# Qwiic_RockBLOCK_9603N.net
KiCad netlist of a schematic drawn in EAGLE
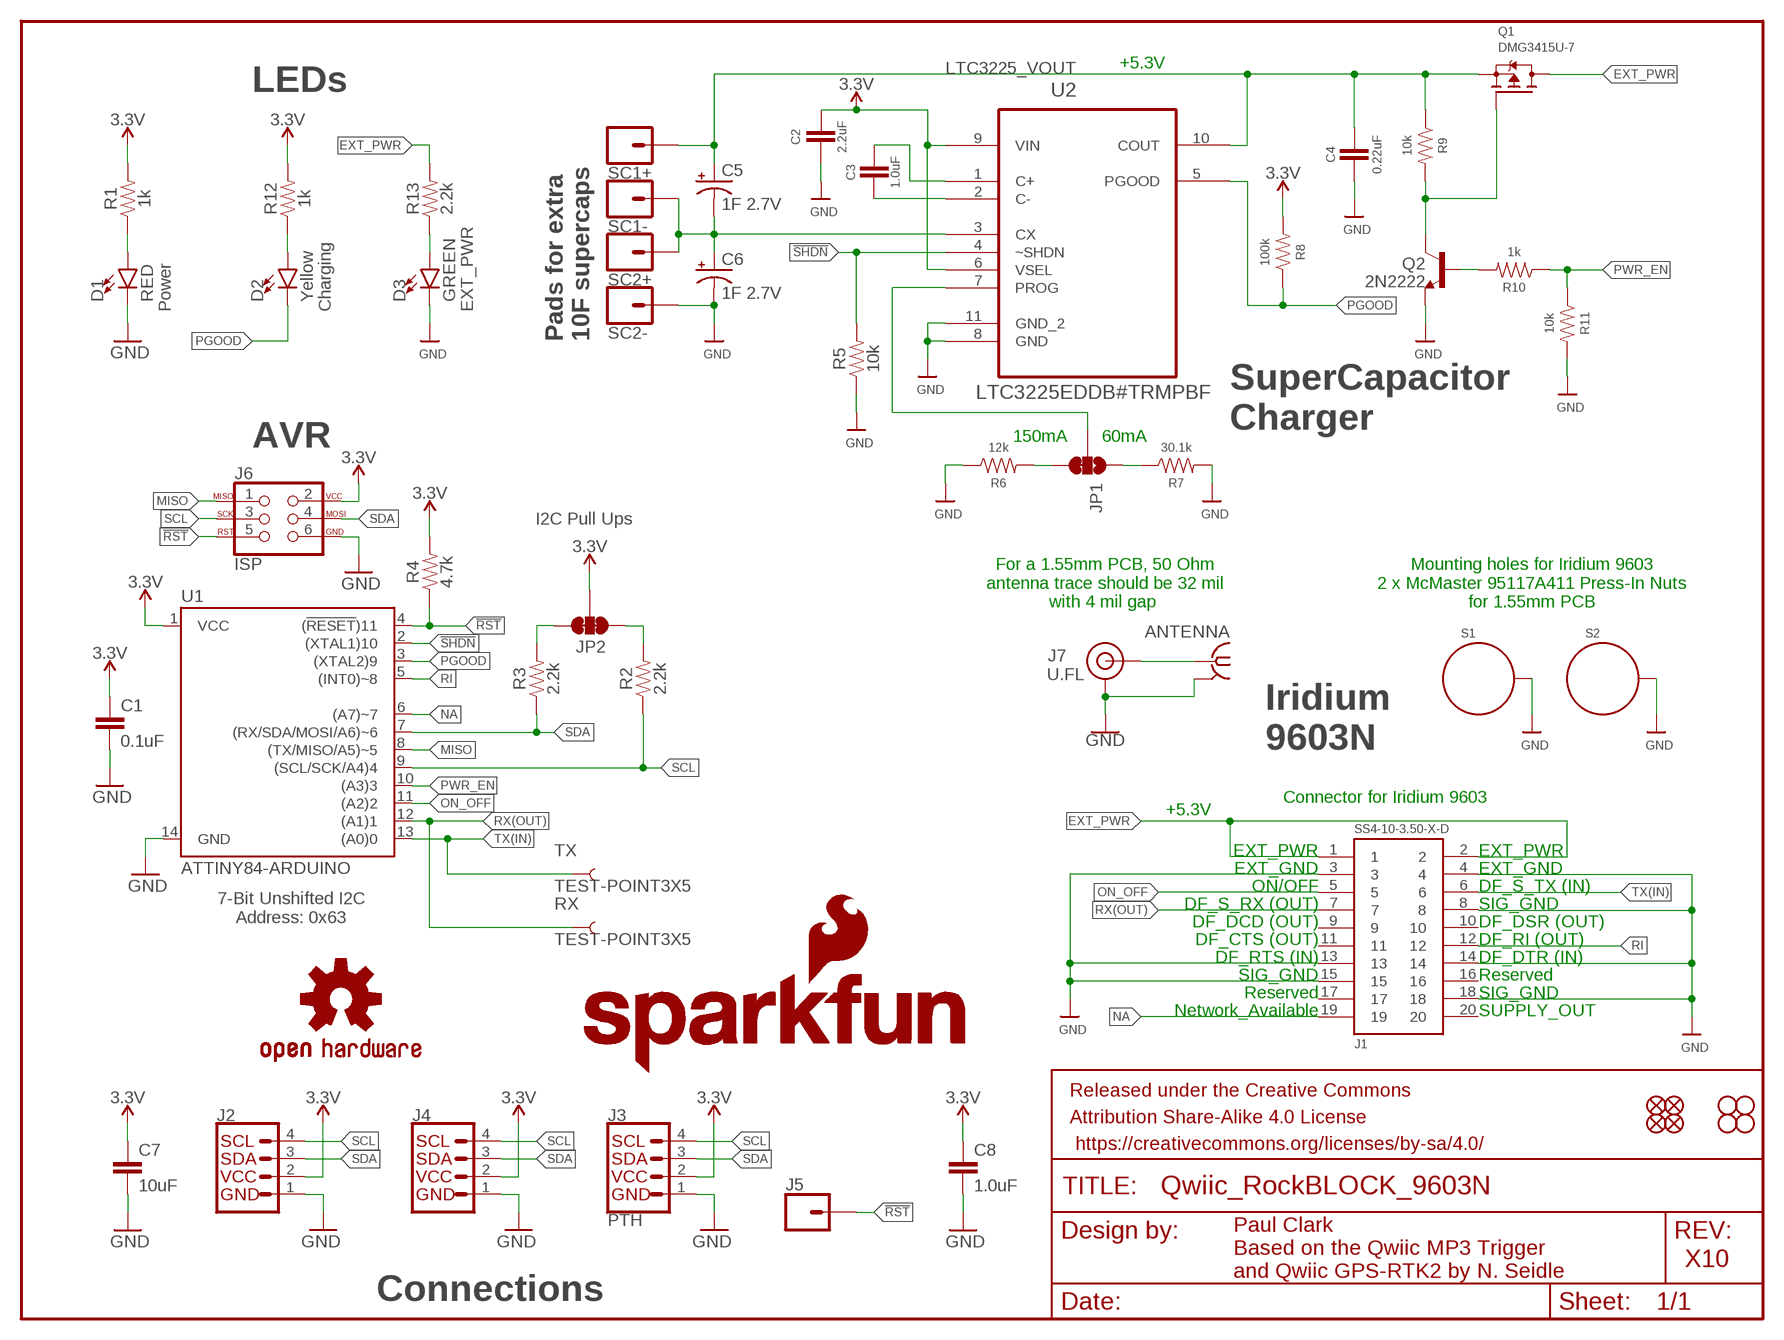
[diagram p0: schematic, sheet 1]

(export (version "E")
  (design (tool "Eeschema 10.0.6"))
  (components
    (comp (ref "ANTENNA")
      (value "SMA-142-0711-821/826")
      (footprint "eagle-import:J502-ND-142-0711-821_826")
      (fields (field (name "MF") "JOHNSON COMPONENTS") (field (name "MPN") "142-0711-821"))
      (libsource (lib "eagle-import") (part "SMA-142-0711-821/826"))
    )
    (comp (ref "C1")
      (value "0.1uF")
      (footprint "eagle-import:0603")
      (libsource (lib "eagle-import") (part "0.1UF-0603-25V-(+80/-20%)"))
    )
    (comp (ref "C2")
      (value "2.2uF")
      (footprint "eagle-import:0603")
      (libsource (lib "eagle-import") (part "2.2UF-0603-10V-20%"))
    )
    (comp (ref "C3")
      (value "1.0uF")
      (footprint "eagle-import:0603")
      (libsource (lib "eagle-import") (part "1.0UF-0603-16V-10%"))
    )
    (comp (ref "C4")
      (value "0.22uF")
      (footprint "eagle-import:0603")
      (libsource (lib "eagle-import") (part "0.22UF-0603-25V-10%"))
    )
    (comp (ref "C5")
      (value "1F 2.7V")
      (footprint "eagle-import:CPOL-RADIAL-1F-2.7V")
      (libsource (lib "eagle-import") (part "1F-2.7V(PTH)CPOL-RADIAL-1H-2.7V"))
    )
    (comp (ref "C6")
      (value "1F 2.7V")
      (footprint "eagle-import:CPOL-RADIAL-1F-2.7V")
      (libsource (lib "eagle-import") (part "1F-2.7V(PTH)CPOL-RADIAL-1H-2.7V"))
    )
    (comp (ref "C7")
      (value "10uF")
      (footprint "eagle-import:0603")
      (libsource (lib "eagle-import") (part "10UF-0603-6.3V-20%"))
    )
    (comp (ref "C8")
      (value "1.0uF")
      (footprint "eagle-import:0603")
      (libsource (lib "eagle-import") (part "1.0UF-0603-16V-10%"))
    )
    (comp (ref "D1")
      (value "RED")
      (footprint "eagle-import:LED-0603")
      (libsource (lib "eagle-import") (part "LED-RED0603"))
    )
    (comp (ref "D2")
      (value "Yellow")
      (footprint "eagle-import:LED-0603")
      (libsource (lib "eagle-import") (part "LED-YELLOW0603"))
    )
    (comp (ref "D3")
      (value "GREEN")
      (footprint "eagle-import:LED-0603")
      (libsource (lib "eagle-import") (part "LED-GREEN0603"))
    )
    (comp (ref "FRAME1")
      (value "FRAME-LETTER")
      (footprint "eagle-import:CREATIVE_COMMONS")
      (libsource (lib "eagle-import") (part "FRAME-LETTER"))
    )
    (comp (ref "J1")
      (value "SS4-10-3.50-X-D")
      (footprint "eagle-import:SS4-10-3.50-X-D")
      (libsource (lib "eagle-import") (part "SS4-10-3.50-X-D"))
    )
    (comp (ref "J2")
      (value "QWIIC_CONNECTORJS-1MM")
      (footprint "eagle-import:1X04_1MM_RA")
      (libsource (lib "eagle-import") (part "QWIIC_CONNECTORJS-1MM"))
    )
    (comp (ref "J3")
      (value "PTH")
      (footprint "eagle-import:1X04_NO_SILK")
      (libsource (lib "eagle-import") (part "I2C_STANDARD_NO_SILK"))
    )
    (comp (ref "J4")
      (value "QWIIC_CONNECTORJS-1MM")
      (footprint "eagle-import:1X04_1MM_RA")
      (libsource (lib "eagle-import") (part "QWIIC_CONNECTORJS-1MM"))
    )
    (comp (ref "J5")
      (value "CONN_01PTH_NO_SILK_YES_STOP")
      (footprint "eagle-import:1X01_NO_SILK")
      (libsource (lib "eagle-import") (part "CONN_01PTH_NO_SILK_YES_STOP"))
    )
    (comp (ref "J6")
      (value "ISP")
      (footprint "eagle-import:2X3_TEST_POINTS")
      (libsource (lib "eagle-import") (part "AVR_SPI_PROG_3X2TESTPOINTS"))
    )
    (comp (ref "J7")
      (value "U.FL")
      (footprint "eagle-import:U.FL")
      (libsource (lib "eagle-import") (part "U.FL2PIN"))
    )
    (comp (ref "JP1")
      (value "JUMPER-PAD-3-2OF3_NC_BY_TRACE_LARGE")
      (footprint "eagle-import:PAD-JUMPER-3-2OF3_NC_BY_TRACE_YES_SILK_LARGE")
      (libsource (lib "eagle-import") (part "JUMPER-PAD-3-2OF3_NC_BY_TRACE_LARGE"))
    )
    (comp (ref "JP2")
      (value "JUMPER-SMT_3_2-NC_TRACE_SILK")
      (footprint "eagle-import:SMT-JUMPER_3_2-NC_TRACE_SILK")
      (libsource (lib "eagle-import") (part "JUMPER-SMT_3_2-NC_TRACE_SILK"))
    )
    (comp (ref "JP3")
      (value "STAND-OFF")
      (footprint "eagle-import:STAND-OFF")
      (libsource (lib "eagle-import") (part "STAND-OFF"))
    )
    (comp (ref "JP4")
      (value "STAND-OFF")
      (footprint "eagle-import:STAND-OFF")
      (libsource (lib "eagle-import") (part "STAND-OFF"))
    )
    (comp (ref "JP5")
      (value "FIDUCIALUFIDUCIAL")
      (footprint "eagle-import:MICRO-FIDUCIAL")
      (libsource (lib "eagle-import") (part "FIDUCIALUFIDUCIAL"))
    )
    (comp (ref "JP6")
      (value "FIDUCIALUFIDUCIAL")
      (footprint "eagle-import:MICRO-FIDUCIAL")
      (libsource (lib "eagle-import") (part "FIDUCIALUFIDUCIAL"))
    )
    (comp (ref "JP7")
      (value "FIDUCIALUFIDUCIAL")
      (footprint "eagle-import:MICRO-FIDUCIAL")
      (libsource (lib "eagle-import") (part "FIDUCIALUFIDUCIAL"))
    )
    (comp (ref "JP8")
      (value "FIDUCIALUFIDUCIAL")
      (footprint "eagle-import:MICRO-FIDUCIAL")
      (libsource (lib "eagle-import") (part "FIDUCIALUFIDUCIAL"))
    )
    (comp (ref "JP9")
      (value "STAND-OFF")
      (footprint "eagle-import:STAND-OFF")
      (libsource (lib "eagle-import") (part "STAND-OFF"))
    )
    (comp (ref "JP10")
      (value "STAND-OFF")
      (footprint "eagle-import:STAND-OFF")
      (libsource (lib "eagle-import") (part "STAND-OFF"))
    )
    (comp (ref "LOGO1")
      (value "OSHW-LOGOMINI")
      (footprint "eagle-import:OSHW-LOGO-MINI")
      (libsource (lib "eagle-import") (part "OSHW-LOGOMINI"))
    )
    (comp (ref "LOGO2")
      (value "SFE_LOGO_NAME.1_INCH")
      (footprint "eagle-import:SFE_LOGO_NAME_.1")
      (libsource (lib "eagle-import") (part "SFE_LOGO_NAME.1_INCH"))
    )
    (comp (ref "LOGO3")
      (value "SFE_LOGO_NAME_FLAME.1_INCH")
      (footprint "eagle-import:SFE_LOGO_NAME_FLAME_.1")
      (libsource (lib "eagle-import") (part "SFE_LOGO_NAME_FLAME.1_INCH"))
    )
    (comp (ref "Q1")
      (value "DMG3415U-7")
      (footprint "eagle-import:SOT23-WIDE")
      (libsource (lib "eagle-import") (part "MOSFET-PWIDE"))
    )
    (comp (ref "Q2")
      (value "2N2222")
      (footprint "eagle-import:SOT23-BEC")
      (libsource (lib "eagle-import") (part "-NPN-SOT23-BECMMBT2222ALT1"))
    )
    (comp (ref "R1")
      (value "1k")
      (footprint "eagle-import:0603")
      (libsource (lib "eagle-import") (part "1KOHM-0603-1/10W-1%"))
    )
    (comp (ref "R2")
      (value "2.2k")
      (footprint "eagle-import:0603")
      (libsource (lib "eagle-import") (part "2.2KOHM-0603-1/10W-1%"))
    )
    (comp (ref "R3")
      (value "2.2k")
      (footprint "eagle-import:0603")
      (libsource (lib "eagle-import") (part "2.2KOHM-0603-1/10W-1%"))
    )
    (comp (ref "R4")
      (value "4.7k")
      (footprint "eagle-import:0603")
      (libsource (lib "eagle-import") (part "4.7KOHM-0603-1/10W-1%"))
    )
    (comp (ref "R5")
      (value "10k")
      (footprint "eagle-import:0603")
      (libsource (lib "eagle-import") (part "10KOHM-0603-1/10W-1%"))
    )
    (comp (ref "R6")
      (value "12k")
      (footprint "eagle-import:0603")
      (libsource (lib "eagle-import") (part "12KOHM-0603-1/10W-1%"))
    )
    (comp (ref "R7")
      (value "30.1k")
      (footprint "eagle-import:0603")
      (libsource (lib "eagle-import") (part "30.1KOHM-0603-1/10W-1%"))
    )
    (comp (ref "R8")
      (value "100k")
      (footprint "eagle-import:0603")
      (libsource (lib "eagle-import") (part "100KOHM-0603-1/10W-1%"))
    )
    (comp (ref "R9")
      (value "10k")
      (footprint "eagle-import:0603")
      (libsource (lib "eagle-import") (part "SparkFun-Resistors_532_10KOHM-0603-1/10W-1%"))
    )
    (comp (ref "R10")
      (value "1k")
      (footprint "eagle-import:0603")
      (libsource (lib "eagle-import") (part "SparkFun-Resistors_532_1KOHM-0603-1/10W-1%"))
    )
    (comp (ref "R11")
      (value "10k")
      (footprint "eagle-import:0603")
      (libsource (lib "eagle-import") (part "SparkFun-Resistors_532_10KOHM-0603-1/10W-1%"))
    )
    (comp (ref "R12")
      (value "1k")
      (footprint "eagle-import:0603")
      (libsource (lib "eagle-import") (part "1KOHM-0603-1/10W-1%"))
    )
    (comp (ref "R13")
      (value "2.2k")
      (footprint "eagle-import:0603")
      (libsource (lib "eagle-import") (part "2.2KOHM-0603-1/10W-1%"))
    )
    (comp (ref "RX")
      (value "TEST-POINT3X5")
      (footprint "eagle-import:PAD.03X.05")
      (libsource (lib "eagle-import") (part "TEST-POINT3X5"))
    )
    (comp (ref "S1")
      (value "STANDOFF_ELECTRICALMCMASTER-95117A411")
      (footprint "eagle-import:STANDOFF-ELECTRICAL-MCMASTER-95117A411")
      (libsource (lib "eagle-import") (part "STANDOFF_ELECTRICALMCMASTER-95117A411"))
    )
    (comp (ref "S2")
      (value "STANDOFF_ELECTRICALMCMASTER-95117A411")
      (footprint "eagle-import:STANDOFF-ELECTRICAL-MCMASTER-95117A411")
      (libsource (lib "eagle-import") (part "STANDOFF_ELECTRICALMCMASTER-95117A411"))
    )
    (comp (ref "SC1+")
      (value "CONN_01PTH_NO_SILK_YES_STOP")
      (footprint "eagle-import:1X01_NO_SILK")
      (libsource (lib "eagle-import") (part "CONN_01PTH_NO_SILK_YES_STOP"))
    )
    (comp (ref "SC1-")
      (value "CONN_01PTH_NO_SILK_YES_STOP")
      (footprint "eagle-import:1X01_NO_SILK")
      (libsource (lib "eagle-import") (part "CONN_01PTH_NO_SILK_YES_STOP"))
    )
    (comp (ref "SC2+")
      (value "CONN_01PTH_NO_SILK_YES_STOP")
      (footprint "eagle-import:1X01_NO_SILK")
      (libsource (lib "eagle-import") (part "CONN_01PTH_NO_SILK_YES_STOP"))
    )
    (comp (ref "SC2-")
      (value "CONN_01PTH_NO_SILK_YES_STOP")
      (footprint "eagle-import:1X01_NO_SILK")
      (libsource (lib "eagle-import") (part "CONN_01PTH_NO_SILK_YES_STOP"))
    )
    (comp (ref "TX")
      (value "TEST-POINT3X5")
      (footprint "eagle-import:PAD.03X.05")
      (libsource (lib "eagle-import") (part "TEST-POINT3X5"))
    )
    (comp (ref "U1")
      (value "ATTINY84-ARDUINO")
      (footprint "eagle-import:SO14")
      (libsource (lib "eagle-import") (part "ATTINY84-ARDUINO"))
    )
    (comp (ref "U2")
      (value "LTC3225EDDB#TRMPBF")
      (footprint "eagle-import:DFN300X200-10L")
      (libsource (lib "eagle-import") (part "LTC3225EDDB-TRMPBFDFN300X200-10L"))
    )
  )
  (nets
    (net (code "1") (name "/LTC3225_VOUT") (class "Default")
      (node (ref "C4") (pin "1") (pinfunction "1_1") (pintype "passive"))
      (node (ref "C5") (pin "+") (pinfunction "+_+") (pintype "passive"))
      (node (ref "Q1") (pin "2") (pinfunction "S_2") (pintype "passive"))
      (node (ref "R9") (pin "1") (pinfunction "1_1") (pintype "passive"))
      (node (ref "SC1+") (pin "1") (pinfunction "1_1") (pintype "passive"))
      (node (ref "U2") (pin "10") (pinfunction "COUT_10") (pintype "output"))
    )
    (net (code "2") (name "/~{RST}") (class "Default")
      (node (ref "J5") (pin "1") (pinfunction "1_1") (pintype "passive"))
      (node (ref "J6") (pin "5") (pinfunction "5_5") (pintype "passive"))
      (node (ref "R4") (pin "1") (pinfunction "1_1") (pintype "passive"))
      (node (ref "U1") (pin "4") (pinfunction "(~{RESET})11_4") (pintype "bidirectional"))
    )
    (net (code "3") (name "/~{SHDN}") (class "Default")
      (node (ref "R5") (pin "2") (pinfunction "2_2") (pintype "passive"))
      (node (ref "U1") (pin "2") (pinfunction "(XTAL1)10_2") (pintype "bidirectional"))
      (node (ref "U2") (pin "4") (pinfunction "~{SHDN}_4") (pintype "input"))
    )
    (net (code "4") (name "3.3V") (class "Default")
      (node (ref "C1") (pin "1") (pinfunction "1_1") (pintype "passive"))
      (node (ref "C2") (pin "1") (pinfunction "1_1") (pintype "passive"))
      (node (ref "C7") (pin "1") (pinfunction "1_1") (pintype "passive"))
      (node (ref "C8") (pin "1") (pinfunction "1_1") (pintype "passive"))
      (node (ref "J2") (pin "2") (pinfunction "2_2") (pintype "power_in"))
      (node (ref "J3") (pin "2") (pinfunction "VCC_2") (pintype "power_in"))
      (node (ref "J4") (pin "2") (pinfunction "2_2") (pintype "power_in"))
      (node (ref "J6") (pin "2") (pinfunction "2_2") (pintype "passive"))
      (node (ref "JP2") (pin "2") (pinfunction "2_2") (pintype "passive"))
      (node (ref "R1") (pin "2") (pinfunction "2_2") (pintype "passive"))
      (node (ref "R12") (pin "2") (pinfunction "2_2") (pintype "passive"))
      (node (ref "R4") (pin "2") (pinfunction "2_2") (pintype "passive"))
      (node (ref "R8") (pin "2") (pinfunction "2_2") (pintype "passive"))
      (node (ref "U1") (pin "1") (pinfunction "VCC_1") (pintype "bidirectional"))
      (node (ref "U2") (pin "6") (pinfunction "VSEL_6") (pintype "input"))
      (node (ref "U2") (pin "9") (pinfunction "VIN_9") (pintype "power_in"))
    )
    (net (code "5") (name "EXT_PWR") (class "Default")
      (node (ref "J1") (pin "1") (pinfunction "1_1") (pintype "bidirectional"))
      (node (ref "J1") (pin "2") (pinfunction "2_2") (pintype "bidirectional"))
      (node (ref "Q1") (pin "3") (pinfunction "D_3") (pintype "passive"))
      (node (ref "R13") (pin "2") (pinfunction "2_2") (pintype "passive"))
    )
    (net (code "6") (name "GND") (class "Default")
      (node (ref "ANTENNA") (pin "G@1") (pinfunction "2_G@1") (pintype "passive"))
      (node (ref "ANTENNA") (pin "G@2") (pinfunction "2_G@2") (pintype "passive"))
      (node (ref "ANTENNA") (pin "G@3") (pinfunction "2_G@3") (pintype "passive"))
      (node (ref "ANTENNA") (pin "G@4") (pinfunction "2_G@4") (pintype "passive"))
      (node (ref "C1") (pin "2") (pinfunction "2_2") (pintype "passive"))
      (node (ref "C2") (pin "2") (pinfunction "2_2") (pintype "passive"))
      (node (ref "C4") (pin "2") (pinfunction "2_2") (pintype "passive"))
      (node (ref "C6") (pin "-") (pinfunction "-_-") (pintype "passive"))
      (node (ref "C7") (pin "2") (pinfunction "2_2") (pintype "passive"))
      (node (ref "C8") (pin "2") (pinfunction "2_2") (pintype "passive"))
      (node (ref "D1") (pin "C") (pinfunction "C_C") (pintype "passive"))
      (node (ref "D3") (pin "C") (pinfunction "C_C") (pintype "passive"))
      (node (ref "J1") (pin "13") (pinfunction "13_13") (pintype "bidirectional"))
      (node (ref "J1") (pin "14") (pinfunction "14_14") (pintype "bidirectional"))
      (node (ref "J1") (pin "15") (pinfunction "15_15") (pintype "bidirectional"))
      (node (ref "J1") (pin "18") (pinfunction "18_18") (pintype "bidirectional"))
      (node (ref "J1") (pin "3") (pinfunction "3_3") (pintype "bidirectional"))
      (node (ref "J1") (pin "4") (pinfunction "4_4") (pintype "bidirectional"))
      (node (ref "J1") (pin "8") (pinfunction "8_8") (pintype "bidirectional"))
      (node (ref "J2") (pin "1") (pinfunction "1_1") (pintype "power_in"))
      (node (ref "J3") (pin "1") (pinfunction "GND_1") (pintype "power_in"))
      (node (ref "J4") (pin "1") (pinfunction "1_1") (pintype "power_in"))
      (node (ref "J6") (pin "6") (pinfunction "6_6") (pintype "passive"))
      (node (ref "J7") (pin "1") (pinfunction "GND_1") (pintype "bidirectional"))
      (node (ref "J7") (pin "2") (pinfunction "GND_2") (pintype "bidirectional"))
      (node (ref "Q2") (pin "E") (pinfunction "E_E") (pintype "passive"))
      (node (ref "R11") (pin "2") (pinfunction "2_2") (pintype "passive"))
      (node (ref "R5") (pin "1") (pinfunction "1_1") (pintype "passive"))
      (node (ref "R6") (pin "1") (pinfunction "1_1") (pintype "passive"))
      (node (ref "R7") (pin "2") (pinfunction "2_2") (pintype "passive"))
      (node (ref "S1") (pin "P1") (pinfunction "P$1_P1") (pintype "bidirectional"))
      (node (ref "S2") (pin "P1") (pinfunction "P$1_P1") (pintype "bidirectional"))
      (node (ref "SC2-") (pin "1") (pinfunction "1_1") (pintype "passive"))
      (node (ref "U1") (pin "14") (pinfunction "GND_14") (pintype "bidirectional"))
      (node (ref "U2") (pin "11") (pinfunction "GND_2_11") (pintype "passive"))
      (node (ref "U2") (pin "8") (pinfunction "GND_8") (pintype "passive"))
    )
    (net (code "7") (name "MISO") (class "Default")
      (node (ref "J6") (pin "1") (pinfunction "1_1") (pintype "passive"))
      (node (ref "U1") (pin "8") (pinfunction "(TX/MISO/A5)~{5}_8") (pintype "bidirectional"))
    )
    (net (code "8") (name "NA") (class "Default")
      (node (ref "J1") (pin "19") (pinfunction "19_19") (pintype "bidirectional"))
      (node (ref "U1") (pin "6") (pinfunction "(A7)~{7}_6") (pintype "bidirectional"))
    )
    (net (code "9") (name "Net-(D1-PadA)") (class "Default")
      (node (ref "D1") (pin "A") (pinfunction "A_A") (pintype "passive"))
      (node (ref "R1") (pin "1") (pinfunction "1_1") (pintype "passive"))
    )
    (net (code "10") (name "Net-(D2-PadA)") (class "Default")
      (node (ref "D2") (pin "A") (pinfunction "A_A") (pintype "passive"))
      (node (ref "R12") (pin "1") (pinfunction "1_1") (pintype "passive"))
    )
    (net (code "11") (name "Net-(D3-PadA)") (class "Default")
      (node (ref "D3") (pin "A") (pinfunction "A_A") (pintype "passive"))
      (node (ref "R13") (pin "1") (pinfunction "1_1") (pintype "passive"))
    )
    (net (code "12") (name "Net-(J7-SIGNAL)") (class "Default")
      (node (ref "ANTENNA") (pin "1") (pinfunction "1_1") (pintype "passive"))
      (node (ref "J7") (pin "FEED") (pinfunction "SIGNAL_FEED") (pintype "bidirectional"))
    )
    (net (code "13") (name "Net-(JP1-Pad1)") (class "Default")
      (node (ref "JP1") (pin "1") (pinfunction "1_1") (pintype "passive"))
      (node (ref "R7") (pin "1") (pinfunction "1_1") (pintype "passive"))
    )
    (net (code "14") (name "Net-(JP1-Pad3)") (class "Default")
      (node (ref "JP1") (pin "3") (pinfunction "3_3") (pintype "passive"))
      (node (ref "R6") (pin "2") (pinfunction "2_2") (pintype "passive"))
    )
    (net (code "15") (name "Net-(JP2-Pad1)") (class "Default")
      (node (ref "JP2") (pin "1") (pinfunction "1_1") (pintype "passive"))
      (node (ref "R2") (pin "2") (pinfunction "2_2") (pintype "passive"))
    )
    (net (code "16") (name "Net-(JP2-Pad3)") (class "Default")
      (node (ref "JP2") (pin "3") (pinfunction "3_3") (pintype "passive"))
      (node (ref "R3") (pin "2") (pinfunction "2_2") (pintype "passive"))
    )
    (net (code "17") (name "Net-(Q1-G)") (class "Default")
      (node (ref "Q1") (pin "1") (pinfunction "G_1") (pintype "passive"))
      (node (ref "Q2") (pin "C") (pinfunction "C_C") (pintype "passive"))
      (node (ref "R9") (pin "2") (pinfunction "2_2") (pintype "passive"))
    )
    (net (code "18") (name "Net-(Q2-PadB)") (class "Default")
      (node (ref "Q2") (pin "B") (pinfunction "B_B") (pintype "passive"))
      (node (ref "R10") (pin "2") (pinfunction "2_2") (pintype "passive"))
    )
    (net (code "19") (name "Net-(U2-C+)") (class "Default")
      (node (ref "C3") (pin "1") (pinfunction "1_1") (pintype "passive"))
      (node (ref "U2") (pin "1") (pinfunction "C+_1") (pintype "passive"))
    )
    (net (code "20") (name "Net-(U2-C-)") (class "Default")
      (node (ref "C3") (pin "2") (pinfunction "2_2") (pintype "passive"))
      (node (ref "U2") (pin "2") (pinfunction "C-_2") (pintype "passive"))
    )
    (net (code "21") (name "Net-(U2-CX)") (class "Default")
      (node (ref "C5") (pin "-") (pinfunction "-_-") (pintype "passive"))
      (node (ref "C6") (pin "+") (pinfunction "+_+") (pintype "passive"))
      (node (ref "SC1-") (pin "1") (pinfunction "1_1") (pintype "passive"))
      (node (ref "SC2+") (pin "1") (pinfunction "1_1") (pintype "passive"))
      (node (ref "U2") (pin "3") (pinfunction "CX_3") (pintype "passive"))
    )
    (net (code "22") (name "Net-(U2-PROG)") (class "Default")
      (node (ref "JP1") (pin "2") (pinfunction "2_2") (pintype "passive"))
      (node (ref "U2") (pin "7") (pinfunction "PROG_7") (pintype "input"))
    )
    (net (code "23") (name "ON_OFF") (class "Default")
      (node (ref "J1") (pin "5") (pinfunction "5_5") (pintype "bidirectional"))
      (node (ref "U1") (pin "11") (pinfunction "(A2)2_11") (pintype "bidirectional"))
    )
    (net (code "24") (name "PGOOD") (class "Default")
      (node (ref "D2") (pin "C") (pinfunction "C_C") (pintype "passive"))
      (node (ref "R8") (pin "1") (pinfunction "1_1") (pintype "passive"))
      (node (ref "U1") (pin "3") (pinfunction "(XTAL2)9_3") (pintype "bidirectional"))
      (node (ref "U2") (pin "5") (pinfunction "PGOOD_5") (pintype "output"))
    )
    (net (code "25") (name "PWR_EN") (class "Default")
      (node (ref "R10") (pin "1") (pinfunction "1_1") (pintype "passive"))
      (node (ref "R11") (pin "1") (pinfunction "1_1") (pintype "passive"))
      (node (ref "U1") (pin "10") (pinfunction "(A3)3_10") (pintype "bidirectional"))
    )
    (net (code "26") (name "RI") (class "Default")
      (node (ref "J1") (pin "12") (pinfunction "12_12") (pintype "bidirectional"))
      (node (ref "U1") (pin "5") (pinfunction "(INT0)~{8}_5") (pintype "bidirectional"))
    )
    (net (code "27") (name "RX(OUT)") (class "Default")
      (node (ref "J1") (pin "7") (pinfunction "7_7") (pintype "bidirectional"))
      (node (ref "RX") (pin "P$1") (pinfunction "1_P$1") (pintype "bidirectional"))
      (node (ref "U1") (pin "12") (pinfunction "(A1)1_12") (pintype "bidirectional"))
    )
    (net (code "28") (name "SCL") (class "Default")
      (node (ref "J2") (pin "4") (pinfunction "4_4") (pintype "passive"))
      (node (ref "J3") (pin "4") (pinfunction "SCL_4") (pintype "passive"))
      (node (ref "J4") (pin "4") (pinfunction "4_4") (pintype "passive"))
      (node (ref "J6") (pin "3") (pinfunction "3_3") (pintype "passive"))
      (node (ref "R2") (pin "1") (pinfunction "1_1") (pintype "passive"))
      (node (ref "U1") (pin "9") (pinfunction "(SCL/SCK/A4)4_9") (pintype "bidirectional"))
    )
    (net (code "29") (name "SDA") (class "Default")
      (node (ref "J2") (pin "3") (pinfunction "3_3") (pintype "passive"))
      (node (ref "J3") (pin "3") (pinfunction "SDA_3") (pintype "passive"))
      (node (ref "J4") (pin "3") (pinfunction "3_3") (pintype "passive"))
      (node (ref "J6") (pin "4") (pinfunction "4_4") (pintype "passive"))
      (node (ref "R3") (pin "1") (pinfunction "1_1") (pintype "passive"))
      (node (ref "U1") (pin "7") (pinfunction "(RX/SDA/MOSI/A6)~{6}_7") (pintype "bidirectional"))
    )
    (net (code "30") (name "TX(IN)") (class "Default")
      (node (ref "J1") (pin "6") (pinfunction "6_6") (pintype "bidirectional"))
      (node (ref "TX") (pin "P$1") (pinfunction "1_P$1") (pintype "bidirectional"))
      (node (ref "U1") (pin "13") (pinfunction "(A0)0_13") (pintype "bidirectional"))
    )
    (net (code "31") (name "unconnected-(J1-Pad9)") (class "Default")
      (node (ref "J1") (pin "9") (pinfunction "9_9") (pintype "bidirectional"))
    )
    (net (code "32") (name "unconnected-(J1-Pad10)") (class "Default")
      (node (ref "J1") (pin "10") (pinfunction "10_10") (pintype "bidirectional"))
    )
    (net (code "33") (name "unconnected-(J1-Pad11)") (class "Default")
      (node (ref "J1") (pin "11") (pinfunction "11_11") (pintype "bidirectional"))
    )
    (net (code "34") (name "unconnected-(J1-Pad16)") (class "Default")
      (node (ref "J1") (pin "16") (pinfunction "16_16") (pintype "bidirectional"))
    )
    (net (code "35") (name "unconnected-(J1-Pad17)") (class "Default")
      (node (ref "J1") (pin "17") (pinfunction "17_17") (pintype "bidirectional"))
    )
    (net (code "36") (name "unconnected-(J1-Pad20)") (class "Default")
      (node (ref "J1") (pin "20") (pinfunction "20_20") (pintype "bidirectional"))
    )
  )
)
